# schematic_r2.net
KiCad netlist of a schematic drawn in EAGLE
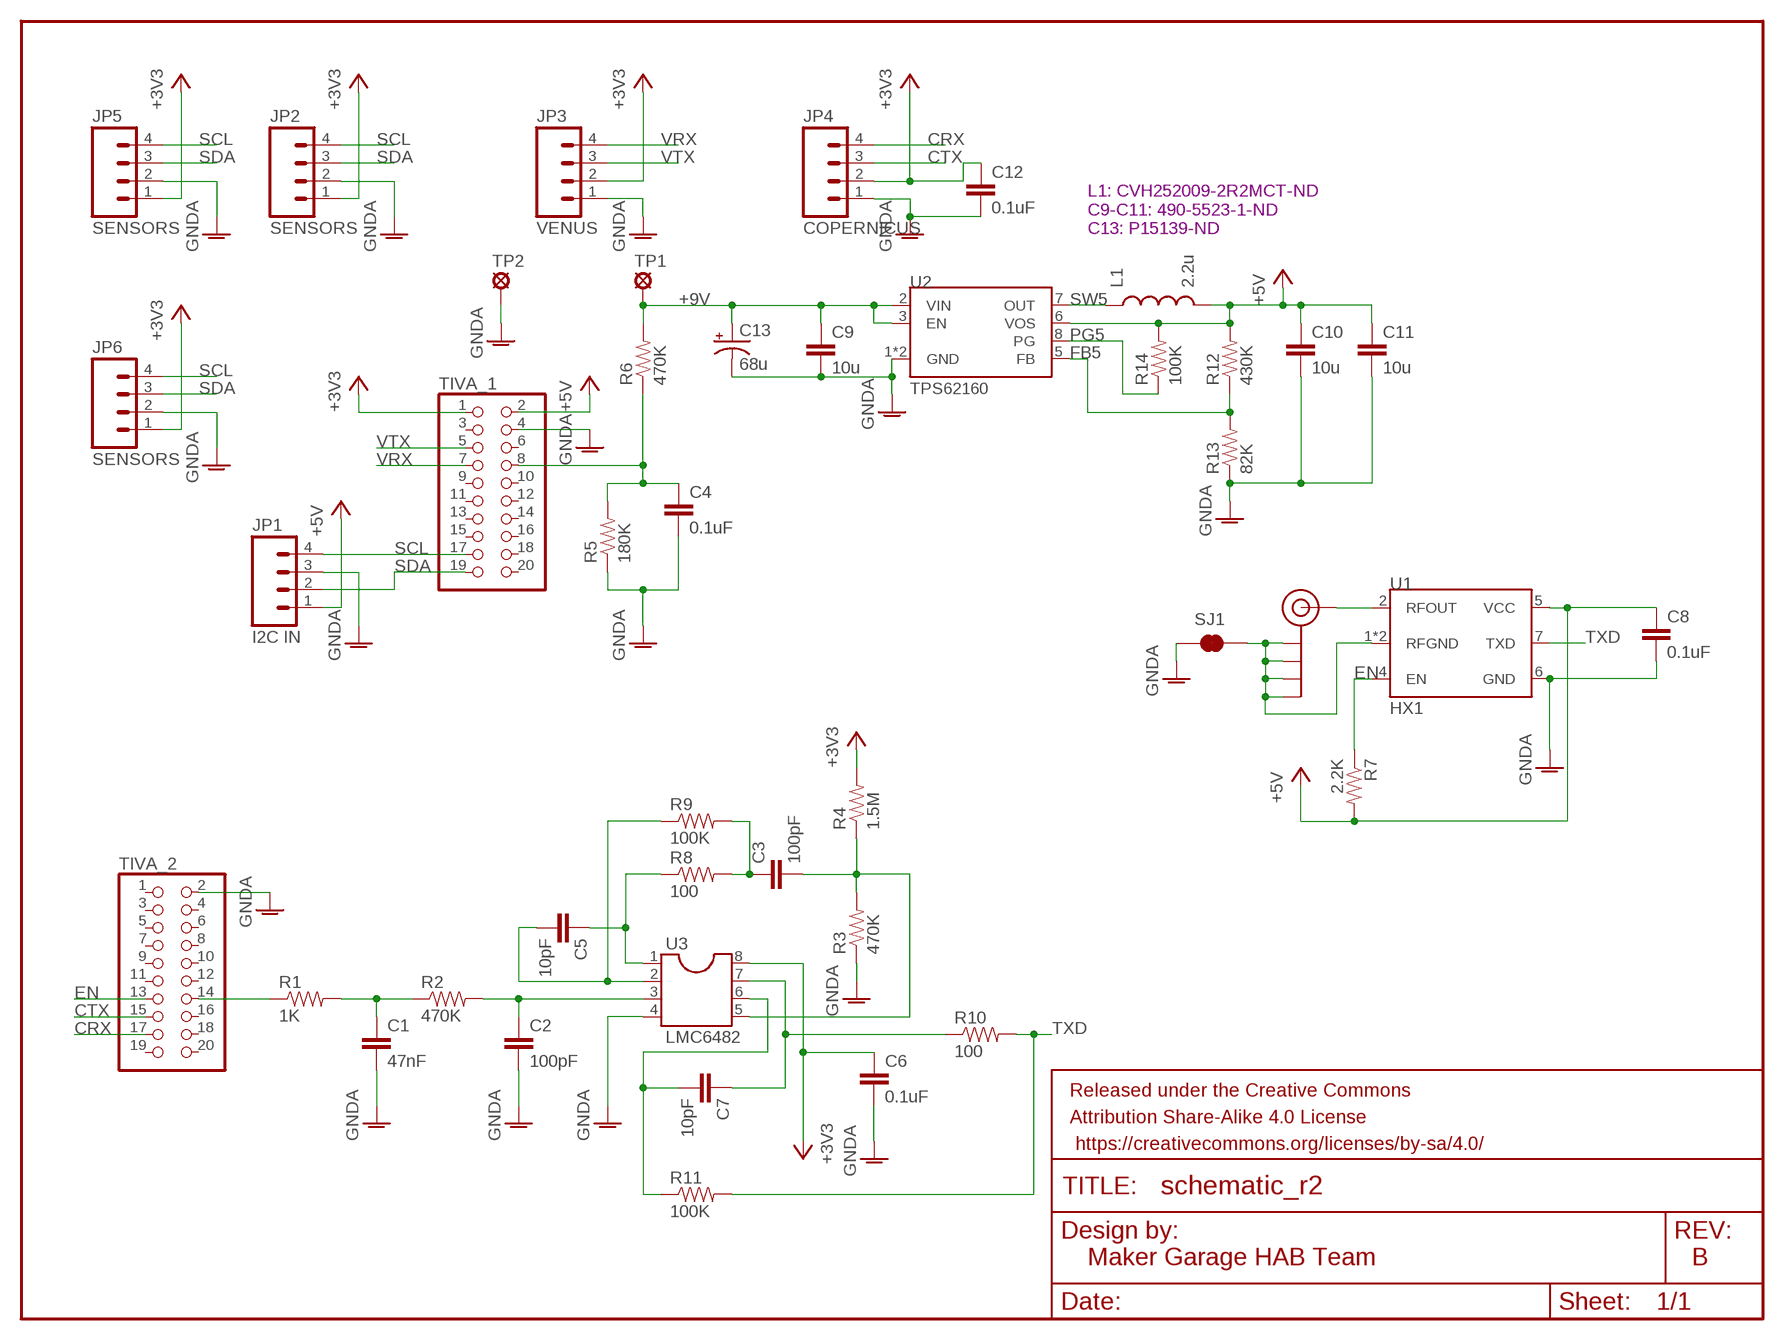
[diagram p0: schematic, sheet 1]

(export (version "E")
  (design (tool "Eeschema 10.0.6"))
  (components
    (comp (ref "C1")
      (value "47nF")
      (footprint "eagle-import:0805")
      (libsource (lib "eagle-import") (part "CAP0805"))
    )
    (comp (ref "C2")
      (value "100pF")
      (footprint "eagle-import:0805")
      (libsource (lib "eagle-import") (part "CAP0805"))
    )
    (comp (ref "C3")
      (value "100pF")
      (footprint "eagle-import:0805")
      (libsource (lib "eagle-import") (part "CAP0805"))
    )
    (comp (ref "C4")
      (value "0.1uF")
      (footprint "eagle-import:0805")
      (libsource (lib "eagle-import") (part "CAP0805"))
    )
    (comp (ref "C5")
      (value "10pF")
      (footprint "eagle-import:0805")
      (libsource (lib "eagle-import") (part "CAP0805"))
    )
    (comp (ref "C6")
      (value "0.1uF")
      (footprint "eagle-import:0805")
      (libsource (lib "eagle-import") (part "CAP0805"))
    )
    (comp (ref "C7")
      (value "10pF")
      (footprint "eagle-import:0805")
      (libsource (lib "eagle-import") (part "CAP0805"))
    )
    (comp (ref "C8")
      (value "0.1uF")
      (footprint "eagle-import:0805")
      (libsource (lib "eagle-import") (part "CAP0805"))
    )
    (comp (ref "C9")
      (value "10u")
      (footprint "eagle-import:0805")
      (libsource (lib "eagle-import") (part "CAP0805"))
    )
    (comp (ref "C10")
      (value "10u")
      (footprint "eagle-import:0805")
      (libsource (lib "eagle-import") (part "CAP0805"))
    )
    (comp (ref "C11")
      (value "10u")
      (footprint "eagle-import:0805")
      (libsource (lib "eagle-import") (part "CAP0805"))
    )
    (comp (ref "C12")
      (value "0.1uF")
      (footprint "eagle-import:0805")
      (libsource (lib "eagle-import") (part "CAP0805"))
    )
    (comp (ref "C13")
      (value "68u")
      (footprint "eagle-import:CPOL-RADIAL-10UF-25V")
      (libsource (lib "eagle-import") (part "CAP_POLPTH2"))
    )
    (comp (ref "FRAME1")
      (value "FRAME-LETTERNO_PACKAGE")
      (footprint "eagle-import:DUMMY")
      (fields (field (name "DESIGNER") "Nobody"))
      (libsource (lib "eagle-import") (part "FRAME-LETTERNO_PACKAGE"))
    )
    (comp (ref "J1")
      (value "SMA_EDGE")
      (footprint "eagle-import:SMA-EDGE")
      (libsource (lib "eagle-import") (part "SMA_EDGE"))
    )
    (comp (ref "JP1")
      (value "I2C IN")
      (footprint "eagle-import:1X04")
      (libsource (lib "eagle-import") (part "M04PTH"))
    )
    (comp (ref "JP2")
      (value "SENSORS")
      (footprint "eagle-import:1X04")
      (libsource (lib "eagle-import") (part "M04PTH"))
    )
    (comp (ref "JP3")
      (value "VENUS")
      (footprint "eagle-import:1X04")
      (libsource (lib "eagle-import") (part "M04PTH"))
    )
    (comp (ref "JP4")
      (value "COPERNICUS")
      (footprint "eagle-import:1X04")
      (libsource (lib "eagle-import") (part "M04PTH"))
    )
    (comp (ref "JP5")
      (value "SENSORS")
      (footprint "eagle-import:1X04")
      (libsource (lib "eagle-import") (part "M04PTH"))
    )
    (comp (ref "JP6")
      (value "SENSORS")
      (footprint "eagle-import:1X04")
      (libsource (lib "eagle-import") (part "M04PTH"))
    )
    (comp (ref "L1")
      (value "2.2u")
      (footprint "eagle-import:1008")
      (libsource (lib "eagle-import") (part "INDUCTOR"))
    )
    (comp (ref "R1")
      (value "1K")
      (footprint "eagle-import:0805")
      (libsource (lib "eagle-import") (part "RESISTOR0805-RES"))
    )
    (comp (ref "R2")
      (value "470K")
      (footprint "eagle-import:0805")
      (libsource (lib "eagle-import") (part "RESISTOR0805-RES"))
    )
    (comp (ref "R3")
      (value "470K")
      (footprint "eagle-import:0805")
      (libsource (lib "eagle-import") (part "RESISTOR0805-RES"))
    )
    (comp (ref "R4")
      (value "1.5M")
      (footprint "eagle-import:0805")
      (libsource (lib "eagle-import") (part "RESISTOR0805-RES"))
    )
    (comp (ref "R5")
      (value "180K")
      (footprint "eagle-import:0805")
      (libsource (lib "eagle-import") (part "RESISTOR0805-RES"))
    )
    (comp (ref "R6")
      (value "470K")
      (footprint "eagle-import:0805")
      (libsource (lib "eagle-import") (part "RESISTOR0805-RES"))
    )
    (comp (ref "R7")
      (value "2.2K")
      (footprint "eagle-import:0805")
      (libsource (lib "eagle-import") (part "RESISTOR0805-RES"))
    )
    (comp (ref "R8")
      (value "100")
      (footprint "eagle-import:0805")
      (libsource (lib "eagle-import") (part "RESISTOR0805-RES"))
    )
    (comp (ref "R9")
      (value "100K")
      (footprint "eagle-import:0805")
      (libsource (lib "eagle-import") (part "RESISTOR0805-RES"))
    )
    (comp (ref "R10")
      (value "100")
      (footprint "eagle-import:0805")
      (libsource (lib "eagle-import") (part "RESISTOR0805-RES"))
    )
    (comp (ref "R11")
      (value "100K")
      (footprint "eagle-import:0805")
      (libsource (lib "eagle-import") (part "RESISTOR0805-RES"))
    )
    (comp (ref "R12")
      (value "430K")
      (footprint "eagle-import:0805")
      (libsource (lib "eagle-import") (part "RESISTOR0805-RES"))
    )
    (comp (ref "R13")
      (value "82K")
      (footprint "eagle-import:0805")
      (libsource (lib "eagle-import") (part "RESISTOR0805-RES"))
    )
    (comp (ref "R14")
      (value "100K")
      (footprint "eagle-import:0805")
      (libsource (lib "eagle-import") (part "RESISTOR0805-RES"))
    )
    (comp (ref "SJ1")
      (value "JUMPER-PAD-2-NC_BY_TRACE")
      (footprint "eagle-import:PAD-JUMPER-2-NC_BY_TRACE_YES_SILK")
      (libsource (lib "eagle-import") (part "JUMPER-PAD-2-NC_BY_TRACE"))
    )
    (comp (ref "TIVA_1")
      (value "PINHD-2X10")
      (footprint "eagle-import:2X10")
      (libsource (lib "eagle-import") (part "PINHD-2X10"))
    )
    (comp (ref "TIVA_2")
      (value "PINHD-2X10")
      (footprint "eagle-import:2X10")
      (libsource (lib "eagle-import") (part "PINHD-2X10"))
    )
    (comp (ref "TP1")
      (value "MCS08")
      (footprint "eagle-import:MCS08")
      (libsource (lib "eagle-import") (part "MCS08"))
    )
    (comp (ref "TP2")
      (value "MCS08")
      (footprint "eagle-import:MCS08")
      (libsource (lib "eagle-import") (part "MCS08"))
    )
    (comp (ref "U1")
      (value "HX1")
      (footprint "eagle-import:1X12")
      (libsource (lib "eagle-import") (part "HX1"))
    )
    (comp (ref "U2")
      (value "TPS62160")
      (footprint "eagle-import:MSOP8")
      (libsource (lib "eagle-import") (part "TPS62160"))
    )
    (comp (ref "U3")
      (value "LMC6482")
      (footprint "eagle-import:DIL08")
      (libsource (lib "eagle-import") (part "DIL8"))
    )
  )
  (nets
    (net (code "1") (name "+3V3") (class "Default")
      (node (ref "C12") (pin "1") (pinfunction "1_1") (pintype "passive"))
      (node (ref "C6") (pin "1") (pinfunction "1_1") (pintype "passive"))
      (node (ref "JP2") (pin "1") (pinfunction "1_1") (pintype "passive"))
      (node (ref "JP3") (pin "2") (pinfunction "2_2") (pintype "passive"))
      (node (ref "JP4") (pin "2") (pinfunction "2_2") (pintype "passive"))
      (node (ref "JP5") (pin "1") (pinfunction "1_1") (pintype "passive"))
      (node (ref "JP6") (pin "1") (pinfunction "1_1") (pintype "passive"))
      (node (ref "R4") (pin "2") (pinfunction "2_2") (pintype "passive"))
      (node (ref "TIVA_1") (pin "1") (pinfunction "1_1") (pintype "passive"))
      (node (ref "U3") (pin "8") (pinfunction "8_8") (pintype "passive"))
    )
    (net (code "2") (name "+5V") (class "Default")
      (node (ref "C10") (pin "1") (pinfunction "1_1") (pintype "passive"))
      (node (ref "C11") (pin "1") (pinfunction "1_1") (pintype "passive"))
      (node (ref "C8") (pin "1") (pinfunction "1_1") (pintype "passive"))
      (node (ref "JP1") (pin "1") (pinfunction "1_1") (pintype "passive"))
      (node (ref "L1") (pin "2") (pinfunction "2_2") (pintype "passive"))
      (node (ref "R12") (pin "2") (pinfunction "2_2") (pintype "passive"))
      (node (ref "R14") (pin "2") (pinfunction "2_2") (pintype "passive"))
      (node (ref "R7") (pin "2") (pinfunction "2_2") (pintype "passive"))
      (node (ref "TIVA_1") (pin "2") (pinfunction "2_2") (pintype "passive"))
      (node (ref "U1") (pin "5") (pinfunction "VCC_5") (pintype "power_in"))
      (node (ref "U2") (pin "6") (pinfunction "VOS_6") (pintype "input"))
    )
    (net (code "3") (name "/+9V") (class "Default")
      (node (ref "C13") (pin "1") (pinfunction "+_1") (pintype "passive"))
      (node (ref "C9") (pin "1") (pinfunction "1_1") (pintype "passive"))
      (node (ref "R6") (pin "2") (pinfunction "2_2") (pintype "passive"))
      (node (ref "TP1") (pin "MP") (pinfunction "MP_MP") (pintype "passive"))
      (node (ref "U2") (pin "2") (pinfunction "VIN_2") (pintype "power_in"))
      (node (ref "U2") (pin "3") (pinfunction "EN_3") (pintype "input"))
    )
    (net (code "4") (name "/CRX") (class "Default")
      (node (ref "JP4") (pin "4") (pinfunction "4_4") (pintype "passive"))
      (node (ref "TIVA_2") (pin "17") (pinfunction "17_17") (pintype "passive"))
    )
    (net (code "5") (name "/CTX") (class "Default")
      (node (ref "JP4") (pin "3") (pinfunction "3_3") (pintype "passive"))
      (node (ref "TIVA_2") (pin "15") (pinfunction "15_15") (pintype "passive"))
    )
    (net (code "6") (name "/EN") (class "Default")
      (node (ref "R7") (pin "1") (pinfunction "1_1") (pintype "passive"))
      (node (ref "TIVA_2") (pin "13") (pinfunction "13_13") (pintype "passive"))
      (node (ref "U1") (pin "4") (pinfunction "EN_4") (pintype "input"))
    )
    (net (code "7") (name "/FB5") (class "Default")
      (node (ref "R12") (pin "1") (pinfunction "1_1") (pintype "passive"))
      (node (ref "R13") (pin "2") (pinfunction "2_2") (pintype "passive"))
      (node (ref "U2") (pin "5") (pinfunction "FB_5") (pintype "input"))
    )
    (net (code "8") (name "/PG5") (class "Default")
      (node (ref "R14") (pin "1") (pinfunction "1_1") (pintype "passive"))
      (node (ref "U2") (pin "8") (pinfunction "PG_8") (pintype "open_collector"))
    )
    (net (code "9") (name "/SCL") (class "Default")
      (node (ref "JP1") (pin "4") (pinfunction "4_4") (pintype "passive"))
      (node (ref "JP2") (pin "4") (pinfunction "4_4") (pintype "passive"))
      (node (ref "JP5") (pin "4") (pinfunction "4_4") (pintype "passive"))
      (node (ref "JP6") (pin "4") (pinfunction "4_4") (pintype "passive"))
      (node (ref "TIVA_1") (pin "17") (pinfunction "17_17") (pintype "passive"))
    )
    (net (code "10") (name "/SDA") (class "Default")
      (node (ref "JP1") (pin "2") (pinfunction "2_2") (pintype "passive"))
      (node (ref "JP2") (pin "3") (pinfunction "3_3") (pintype "passive"))
      (node (ref "JP5") (pin "3") (pinfunction "3_3") (pintype "passive"))
      (node (ref "JP6") (pin "3") (pinfunction "3_3") (pintype "passive"))
      (node (ref "TIVA_1") (pin "19") (pinfunction "19_19") (pintype "passive"))
    )
    (net (code "11") (name "/SW5") (class "Default")
      (node (ref "L1") (pin "1") (pinfunction "1_1") (pintype "passive"))
      (node (ref "U2") (pin "7") (pinfunction "OUT_7") (pintype "output"))
    )
    (net (code "12") (name "/TXD") (class "Default")
      (node (ref "R10") (pin "2") (pinfunction "2_2") (pintype "passive"))
      (node (ref "R11") (pin "2") (pinfunction "2_2") (pintype "passive"))
      (node (ref "U1") (pin "7") (pinfunction "TXD_7") (pintype "input"))
    )
    (net (code "13") (name "/VRX") (class "Default")
      (node (ref "JP3") (pin "4") (pinfunction "4_4") (pintype "passive"))
      (node (ref "TIVA_1") (pin "7") (pinfunction "7_7") (pintype "passive"))
    )
    (net (code "14") (name "/VTX") (class "Default")
      (node (ref "JP3") (pin "3") (pinfunction "3_3") (pintype "passive"))
      (node (ref "TIVA_1") (pin "5") (pinfunction "5_5") (pintype "passive"))
    )
    (net (code "15") (name "GNDA") (class "Default")
      (node (ref "C1") (pin "2") (pinfunction "2_2") (pintype "passive"))
      (node (ref "C10") (pin "2") (pinfunction "2_2") (pintype "passive"))
      (node (ref "C11") (pin "2") (pinfunction "2_2") (pintype "passive"))
      (node (ref "C12") (pin "2") (pinfunction "2_2") (pintype "passive"))
      (node (ref "C13") (pin "2") (pinfunction "-_2") (pintype "passive"))
      (node (ref "C2") (pin "2") (pinfunction "2_2") (pintype "passive"))
      (node (ref "C4") (pin "2") (pinfunction "2_2") (pintype "passive"))
      (node (ref "C6") (pin "2") (pinfunction "2_2") (pintype "passive"))
      (node (ref "C8") (pin "2") (pinfunction "2_2") (pintype "passive"))
      (node (ref "C9") (pin "2") (pinfunction "2_2") (pintype "passive"))
      (node (ref "JP1") (pin "3") (pinfunction "3_3") (pintype "passive"))
      (node (ref "JP2") (pin "2") (pinfunction "2_2") (pintype "passive"))
      (node (ref "JP3") (pin "1") (pinfunction "1_1") (pintype "passive"))
      (node (ref "JP4") (pin "1") (pinfunction "1_1") (pintype "passive"))
      (node (ref "JP5") (pin "2") (pinfunction "2_2") (pintype "passive"))
      (node (ref "JP6") (pin "2") (pinfunction "2_2") (pintype "passive"))
      (node (ref "R13") (pin "1") (pinfunction "1_1") (pintype "passive"))
      (node (ref "R3") (pin "1") (pinfunction "1_1") (pintype "passive"))
      (node (ref "R5") (pin "1") (pinfunction "1_1") (pintype "passive"))
      (node (ref "SJ1") (pin "1") (pinfunction "1_1") (pintype "passive"))
      (node (ref "TIVA_1") (pin "4") (pinfunction "4_4") (pintype "passive"))
      (node (ref "TIVA_2") (pin "2") (pinfunction "2_2") (pintype "passive"))
      (node (ref "TP2") (pin "MP") (pinfunction "MP_MP") (pintype "passive"))
      (node (ref "U1") (pin "6") (pinfunction "GND_6") (pintype "power_in"))
      (node (ref "U2") (pin "1") (pinfunction "GND_1") (pintype "power_in"))
      (node (ref "U2") (pin "4") (pinfunction "GND_4") (pintype "power_in"))
      (node (ref "U3") (pin "4") (pinfunction "4_4") (pintype "passive"))
    )
    (net (code "16") (name "Net-(C1-Pad1)") (class "Default")
      (node (ref "C1") (pin "1") (pinfunction "1_1") (pintype "passive"))
      (node (ref "R1") (pin "2") (pinfunction "2_2") (pintype "passive"))
      (node (ref "R2") (pin "1") (pinfunction "1_1") (pintype "passive"))
    )
    (net (code "17") (name "Net-(C2-Pad1)") (class "Default")
      (node (ref "C2") (pin "1") (pinfunction "1_1") (pintype "passive"))
      (node (ref "R2") (pin "2") (pinfunction "2_2") (pintype "passive"))
      (node (ref "U3") (pin "3") (pinfunction "3_3") (pintype "passive"))
    )
    (net (code "18") (name "Net-(C3-Pad1)") (class "Default")
      (node (ref "C3") (pin "1") (pinfunction "1_1") (pintype "passive"))
      (node (ref "R8") (pin "2") (pinfunction "2_2") (pintype "passive"))
      (node (ref "R9") (pin "2") (pinfunction "2_2") (pintype "passive"))
    )
    (net (code "19") (name "Net-(C3-Pad2)") (class "Default")
      (node (ref "C3") (pin "2") (pinfunction "2_2") (pintype "passive"))
      (node (ref "R3") (pin "2") (pinfunction "2_2") (pintype "passive"))
      (node (ref "R4") (pin "1") (pinfunction "1_1") (pintype "passive"))
      (node (ref "U3") (pin "5") (pinfunction "5_5") (pintype "passive"))
    )
    (net (code "20") (name "Net-(C4-Pad1)") (class "Default")
      (node (ref "C4") (pin "1") (pinfunction "1_1") (pintype "passive"))
      (node (ref "R5") (pin "2") (pinfunction "2_2") (pintype "passive"))
      (node (ref "R6") (pin "1") (pinfunction "1_1") (pintype "passive"))
      (node (ref "TIVA_1") (pin "8") (pinfunction "8_8") (pintype "passive"))
    )
    (net (code "21") (name "Net-(C5-Pad1)") (class "Default")
      (node (ref "C5") (pin "1") (pinfunction "1_1") (pintype "passive"))
      (node (ref "R8") (pin "1") (pinfunction "1_1") (pintype "passive"))
      (node (ref "U3") (pin "1") (pinfunction "1_1") (pintype "passive"))
    )
    (net (code "22") (name "Net-(C5-Pad2)") (class "Default")
      (node (ref "C5") (pin "2") (pinfunction "2_2") (pintype "passive"))
      (node (ref "R9") (pin "1") (pinfunction "1_1") (pintype "passive"))
      (node (ref "U3") (pin "2") (pinfunction "2_2") (pintype "passive"))
    )
    (net (code "23") (name "Net-(C7-Pad1)") (class "Default")
      (node (ref "C7") (pin "1") (pinfunction "1_1") (pintype "passive"))
      (node (ref "R10") (pin "1") (pinfunction "1_1") (pintype "passive"))
      (node (ref "U3") (pin "7") (pinfunction "7_7") (pintype "passive"))
    )
    (net (code "24") (name "Net-(C7-Pad2)") (class "Default")
      (node (ref "C7") (pin "2") (pinfunction "2_2") (pintype "passive"))
      (node (ref "R11") (pin "1") (pinfunction "1_1") (pintype "passive"))
      (node (ref "U3") (pin "6") (pinfunction "6_6") (pintype "passive"))
    )
    (net (code "25") (name "Net-(J1-GND-PadGND@0)") (class "Default")
      (node (ref "J1") (pin "GND@0") (pinfunction "GND_GND@0") (pintype "bidirectional"))
      (node (ref "J1") (pin "GND@1") (pinfunction "GND_GND@1") (pintype "bidirectional"))
      (node (ref "J1") (pin "GND@2") (pinfunction "GND_GND@2") (pintype "bidirectional"))
      (node (ref "J1") (pin "GND@3") (pinfunction "GND_GND@3") (pintype "bidirectional"))
      (node (ref "SJ1") (pin "2") (pinfunction "2_2") (pintype "passive"))
      (node (ref "U1") (pin "1") (pinfunction "RFGND_1") (pintype "power_in"))
      (node (ref "U1") (pin "3") (pinfunction "RFGND_3") (pintype "power_in"))
    )
    (net (code "26") (name "Net-(J1-SIGNAL)") (class "Default")
      (node (ref "J1") (pin "SIG") (pinfunction "SIGNAL_SIG") (pintype "bidirectional"))
      (node (ref "U1") (pin "2") (pinfunction "RFOUT_2") (pintype "output"))
    )
    (net (code "27") (name "Net-(R1-Pad1)") (class "Default")
      (node (ref "R1") (pin "1") (pinfunction "1_1") (pintype "passive"))
      (node (ref "TIVA_2") (pin "14") (pinfunction "14_14") (pintype "passive"))
    )
    (net (code "28") (name "unconnected-(TIVA_1-Pad3)") (class "Default")
      (node (ref "TIVA_1") (pin "3") (pinfunction "3_3") (pintype "passive"))
    )
    (net (code "29") (name "unconnected-(TIVA_1-Pad6)") (class "Default")
      (node (ref "TIVA_1") (pin "6") (pinfunction "6_6") (pintype "passive"))
    )
    (net (code "30") (name "unconnected-(TIVA_1-Pad9)") (class "Default")
      (node (ref "TIVA_1") (pin "9") (pinfunction "9_9") (pintype "passive"))
    )
    (net (code "31") (name "unconnected-(TIVA_1-Pad10)") (class "Default")
      (node (ref "TIVA_1") (pin "10") (pinfunction "10_10") (pintype "passive"))
    )
    (net (code "32") (name "unconnected-(TIVA_1-Pad11)") (class "Default")
      (node (ref "TIVA_1") (pin "11") (pinfunction "11_11") (pintype "passive"))
    )
    (net (code "33") (name "unconnected-(TIVA_1-Pad12)") (class "Default")
      (node (ref "TIVA_1") (pin "12") (pinfunction "12_12") (pintype "passive"))
    )
    (net (code "34") (name "unconnected-(TIVA_1-Pad13)") (class "Default")
      (node (ref "TIVA_1") (pin "13") (pinfunction "13_13") (pintype "passive"))
    )
    (net (code "35") (name "unconnected-(TIVA_1-Pad14)") (class "Default")
      (node (ref "TIVA_1") (pin "14") (pinfunction "14_14") (pintype "passive"))
    )
    (net (code "36") (name "unconnected-(TIVA_1-Pad15)") (class "Default")
      (node (ref "TIVA_1") (pin "15") (pinfunction "15_15") (pintype "passive"))
    )
    (net (code "37") (name "unconnected-(TIVA_1-Pad16)") (class "Default")
      (node (ref "TIVA_1") (pin "16") (pinfunction "16_16") (pintype "passive"))
    )
    (net (code "38") (name "unconnected-(TIVA_1-Pad18)") (class "Default")
      (node (ref "TIVA_1") (pin "18") (pinfunction "18_18") (pintype "passive"))
    )
    (net (code "39") (name "unconnected-(TIVA_1-Pad20)") (class "Default")
      (node (ref "TIVA_1") (pin "20") (pinfunction "20_20") (pintype "passive"))
    )
    (net (code "40") (name "unconnected-(TIVA_2-Pad1)") (class "Default")
      (node (ref "TIVA_2") (pin "1") (pinfunction "1_1") (pintype "passive"))
    )
    (net (code "41") (name "unconnected-(TIVA_2-Pad3)") (class "Default")
      (node (ref "TIVA_2") (pin "3") (pinfunction "3_3") (pintype "passive"))
    )
    (net (code "42") (name "unconnected-(TIVA_2-Pad4)") (class "Default")
      (node (ref "TIVA_2") (pin "4") (pinfunction "4_4") (pintype "passive"))
    )
    (net (code "43") (name "unconnected-(TIVA_2-Pad5)") (class "Default")
      (node (ref "TIVA_2") (pin "5") (pinfunction "5_5") (pintype "passive"))
    )
    (net (code "44") (name "unconnected-(TIVA_2-Pad6)") (class "Default")
      (node (ref "TIVA_2") (pin "6") (pinfunction "6_6") (pintype "passive"))
    )
    (net (code "45") (name "unconnected-(TIVA_2-Pad7)") (class "Default")
      (node (ref "TIVA_2") (pin "7") (pinfunction "7_7") (pintype "passive"))
    )
    (net (code "46") (name "unconnected-(TIVA_2-Pad8)") (class "Default")
      (node (ref "TIVA_2") (pin "8") (pinfunction "8_8") (pintype "passive"))
    )
    (net (code "47") (name "unconnected-(TIVA_2-Pad9)") (class "Default")
      (node (ref "TIVA_2") (pin "9") (pinfunction "9_9") (pintype "passive"))
    )
    (net (code "48") (name "unconnected-(TIVA_2-Pad10)") (class "Default")
      (node (ref "TIVA_2") (pin "10") (pinfunction "10_10") (pintype "passive"))
    )
    (net (code "49") (name "unconnected-(TIVA_2-Pad11)") (class "Default")
      (node (ref "TIVA_2") (pin "11") (pinfunction "11_11") (pintype "passive"))
    )
    (net (code "50") (name "unconnected-(TIVA_2-Pad12)") (class "Default")
      (node (ref "TIVA_2") (pin "12") (pinfunction "12_12") (pintype "passive"))
    )
    (net (code "51") (name "unconnected-(TIVA_2-Pad16)") (class "Default")
      (node (ref "TIVA_2") (pin "16") (pinfunction "16_16") (pintype "passive"))
    )
    (net (code "52") (name "unconnected-(TIVA_2-Pad18)") (class "Default")
      (node (ref "TIVA_2") (pin "18") (pinfunction "18_18") (pintype "passive"))
    )
    (net (code "53") (name "unconnected-(TIVA_2-Pad19)") (class "Default")
      (node (ref "TIVA_2") (pin "19") (pinfunction "19_19") (pintype "passive"))
    )
    (net (code "54") (name "unconnected-(TIVA_2-Pad20)") (class "Default")
      (node (ref "TIVA_2") (pin "20") (pinfunction "20_20") (pintype "passive"))
    )
  )
)
